# R202X.net
KiCad netlist of a schematic drawn in EAGLE
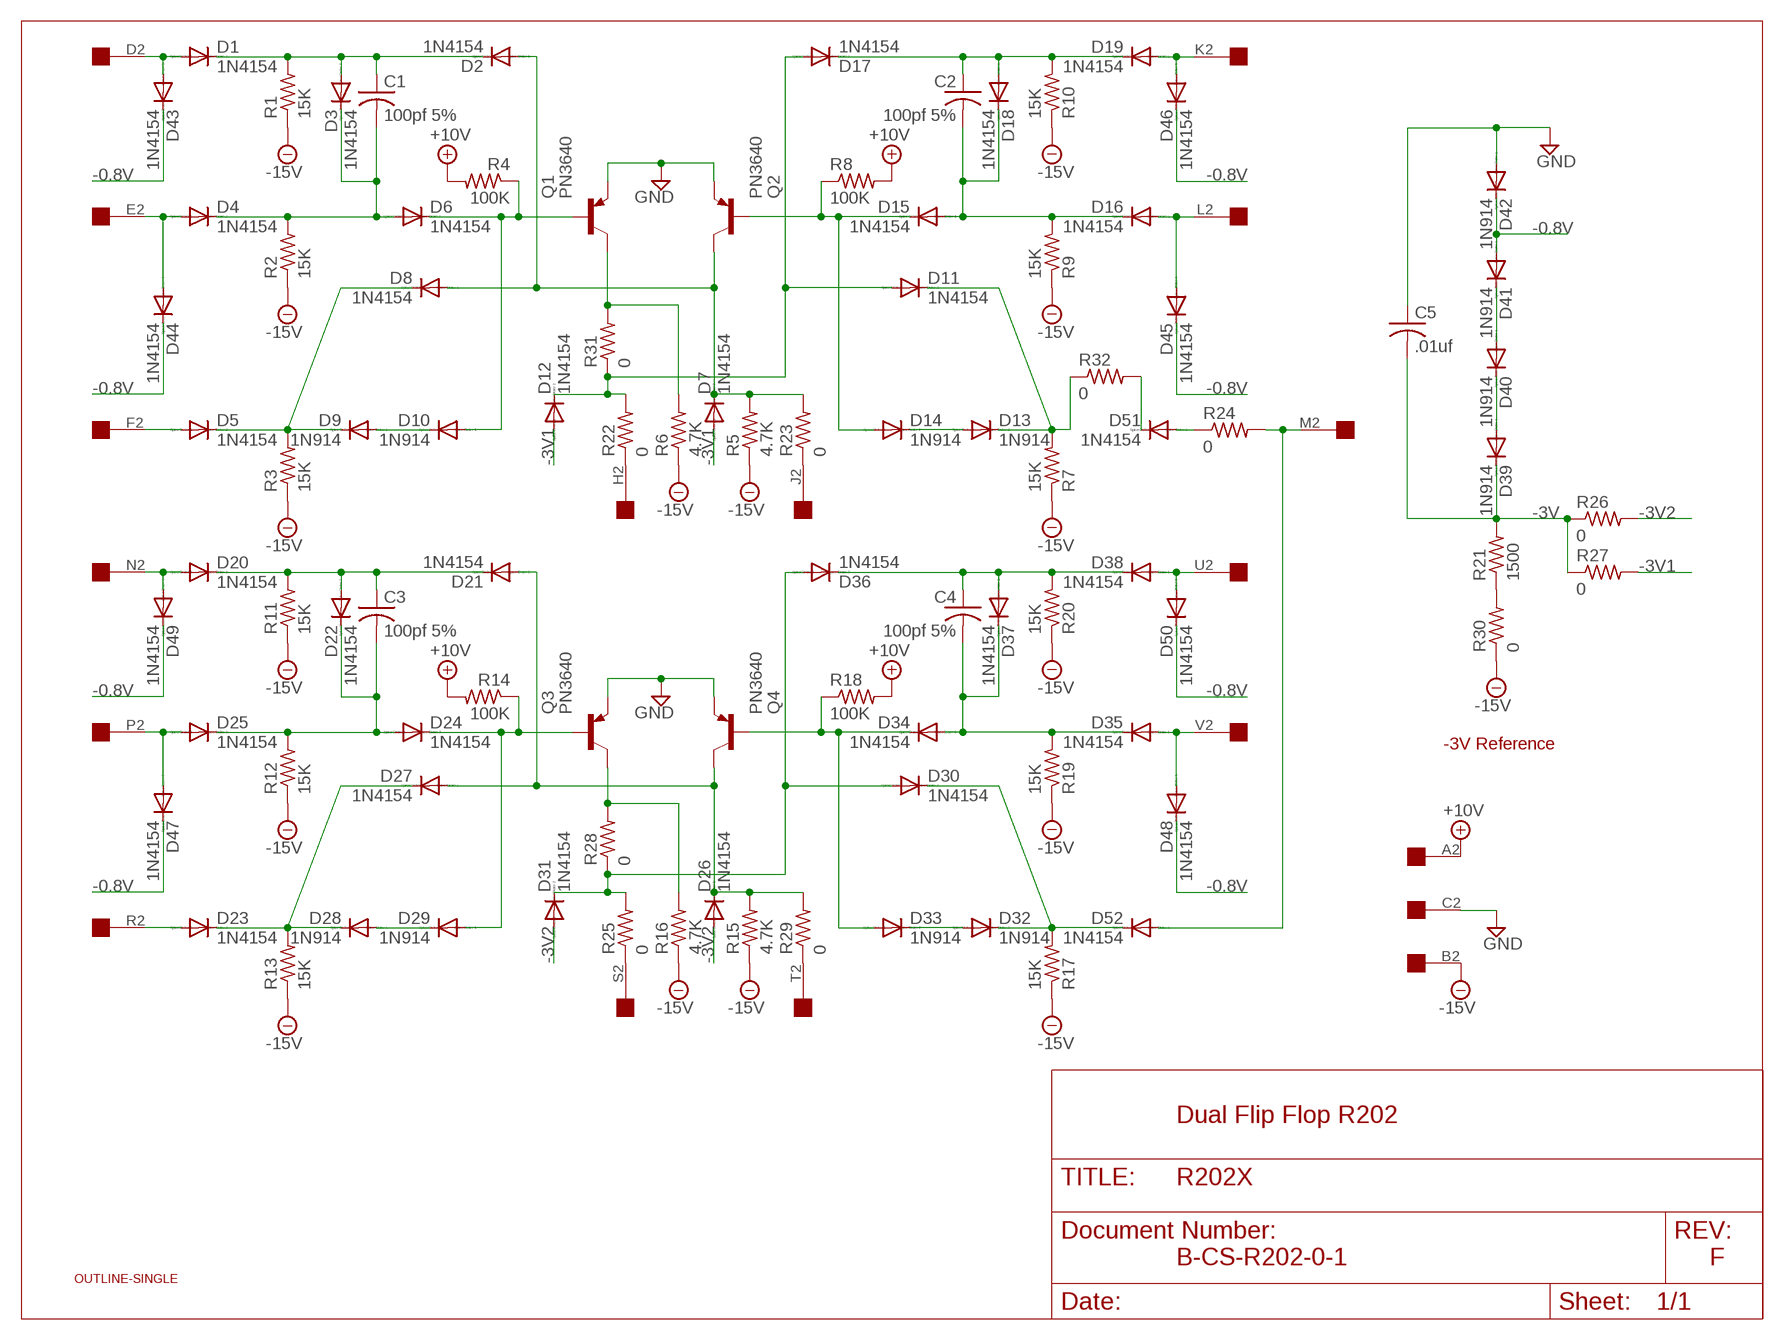
[diagram p0: schematic, sheet 1]

(export (version "E")
  (design (tool "Eeschema 10.0.6"))
  (components
    (comp (ref "C1")
      (value "100pf 5%")
      (footprint "eagle-import:C050-025X075")
      (libsource (lib "eagle-import") (part "C-US050-025X075"))
    )
    (comp (ref "C2")
      (value "100pf 5%")
      (footprint "eagle-import:C050-025X075")
      (libsource (lib "eagle-import") (part "C-US050-025X075"))
    )
    (comp (ref "C3")
      (value "100pf 5%")
      (footprint "eagle-import:C050-025X075")
      (libsource (lib "eagle-import") (part "C-US050-025X075"))
    )
    (comp (ref "C4")
      (value "100pf 5%")
      (footprint "eagle-import:C050-025X075")
      (libsource (lib "eagle-import") (part "C-US050-025X075"))
    )
    (comp (ref "C5")
      (value ".01uf")
      (footprint "eagle-import:C050-025X075")
      (libsource (lib "eagle-import") (part "C-US050-025X075"))
    )
    (comp (ref "D1")
      (value "1N4154")
      (footprint "eagle-import:DO35-10")
      (libsource (lib "eagle-import") (part "1N4148DO35-10"))
    )
    (comp (ref "D2")
      (value "1N4154")
      (footprint "eagle-import:DO35-10")
      (libsource (lib "eagle-import") (part "1N4148DO35-10"))
    )
    (comp (ref "D3")
      (value "1N4154")
      (footprint "eagle-import:DO35-10")
      (libsource (lib "eagle-import") (part "1N4148DO35-10"))
    )
    (comp (ref "D4")
      (value "1N4154")
      (footprint "eagle-import:DO35-10")
      (libsource (lib "eagle-import") (part "1N4148DO35-10"))
    )
    (comp (ref "D5")
      (value "1N4154")
      (footprint "eagle-import:DO35-10")
      (libsource (lib "eagle-import") (part "1N4148DO35-10"))
    )
    (comp (ref "D6")
      (value "1N4154")
      (footprint "eagle-import:DO35-10")
      (libsource (lib "eagle-import") (part "1N4148DO35-10"))
    )
    (comp (ref "D7")
      (value "1N4154")
      (footprint "eagle-import:DO35-10")
      (libsource (lib "eagle-import") (part "1N4148DO35-10"))
    )
    (comp (ref "D8")
      (value "1N4154")
      (footprint "eagle-import:DO35-10")
      (libsource (lib "eagle-import") (part "1N4148DO35-10"))
    )
    (comp (ref "D9")
      (value "1N914")
      (footprint "eagle-import:DO35-10")
      (libsource (lib "eagle-import") (part "1N4148DO35-10"))
    )
    (comp (ref "D10")
      (value "1N914")
      (footprint "eagle-import:DO35-10")
      (libsource (lib "eagle-import") (part "1N4148DO35-10"))
    )
    (comp (ref "D11")
      (value "1N4154")
      (footprint "eagle-import:DO35-10")
      (libsource (lib "eagle-import") (part "1N4148DO35-10"))
    )
    (comp (ref "D12")
      (value "1N4154")
      (footprint "eagle-import:DO35-10")
      (libsource (lib "eagle-import") (part "1N4148DO35-10"))
    )
    (comp (ref "D13")
      (value "1N914")
      (footprint "eagle-import:DO35-10")
      (libsource (lib "eagle-import") (part "1N4148DO35-10"))
    )
    (comp (ref "D14")
      (value "1N914")
      (footprint "eagle-import:DO35-10")
      (libsource (lib "eagle-import") (part "1N4148DO35-10"))
    )
    (comp (ref "D15")
      (value "1N4154")
      (footprint "eagle-import:DO35-10")
      (libsource (lib "eagle-import") (part "1N4148DO35-10"))
    )
    (comp (ref "D16")
      (value "1N4154")
      (footprint "eagle-import:DO35-10")
      (libsource (lib "eagle-import") (part "1N4148DO35-10"))
    )
    (comp (ref "D17")
      (value "1N4154")
      (footprint "eagle-import:DO35-10")
      (libsource (lib "eagle-import") (part "1N4148DO35-10"))
    )
    (comp (ref "D18")
      (value "1N4154")
      (footprint "eagle-import:DO35-10")
      (libsource (lib "eagle-import") (part "1N4148DO35-10"))
    )
    (comp (ref "D19")
      (value "1N4154")
      (footprint "eagle-import:DO35-10")
      (libsource (lib "eagle-import") (part "1N4148DO35-10"))
    )
    (comp (ref "D20")
      (value "1N4154")
      (footprint "eagle-import:DO35-10")
      (libsource (lib "eagle-import") (part "1N4148DO35-10"))
    )
    (comp (ref "D21")
      (value "1N4154")
      (footprint "eagle-import:DO35-10")
      (libsource (lib "eagle-import") (part "1N4148DO35-10"))
    )
    (comp (ref "D22")
      (value "1N4154")
      (footprint "eagle-import:DO35-10")
      (libsource (lib "eagle-import") (part "1N4148DO35-10"))
    )
    (comp (ref "D23")
      (value "1N4154")
      (footprint "eagle-import:DO35-10")
      (libsource (lib "eagle-import") (part "1N4148DO35-10"))
    )
    (comp (ref "D24")
      (value "1N4154")
      (footprint "eagle-import:DO35-10")
      (libsource (lib "eagle-import") (part "1N4148DO35-10"))
    )
    (comp (ref "D25")
      (value "1N4154")
      (footprint "eagle-import:DO35-10")
      (libsource (lib "eagle-import") (part "1N4148DO35-10"))
    )
    (comp (ref "D26")
      (value "1N4154")
      (footprint "eagle-import:DO35-10")
      (libsource (lib "eagle-import") (part "1N4148DO35-10"))
    )
    (comp (ref "D27")
      (value "1N4154")
      (footprint "eagle-import:DO35-10")
      (libsource (lib "eagle-import") (part "1N4148DO35-10"))
    )
    (comp (ref "D28")
      (value "1N914")
      (footprint "eagle-import:DO35-10")
      (libsource (lib "eagle-import") (part "1N4148DO35-10"))
    )
    (comp (ref "D29")
      (value "1N914")
      (footprint "eagle-import:DO35-10")
      (libsource (lib "eagle-import") (part "1N4148DO35-10"))
    )
    (comp (ref "D30")
      (value "1N4154")
      (footprint "eagle-import:DO35-10")
      (libsource (lib "eagle-import") (part "1N4148DO35-10"))
    )
    (comp (ref "D31")
      (value "1N4154")
      (footprint "eagle-import:DO35-10")
      (libsource (lib "eagle-import") (part "1N4148DO35-10"))
    )
    (comp (ref "D32")
      (value "1N914")
      (footprint "eagle-import:DO35-10")
      (libsource (lib "eagle-import") (part "1N4148DO35-10"))
    )
    (comp (ref "D33")
      (value "1N914")
      (footprint "eagle-import:DO35-10")
      (libsource (lib "eagle-import") (part "1N4148DO35-10"))
    )
    (comp (ref "D34")
      (value "1N4154")
      (footprint "eagle-import:DO35-10")
      (libsource (lib "eagle-import") (part "1N4148DO35-10"))
    )
    (comp (ref "D35")
      (value "1N4154")
      (footprint "eagle-import:DO35-10")
      (libsource (lib "eagle-import") (part "1N4148DO35-10"))
    )
    (comp (ref "D36")
      (value "1N4154")
      (footprint "eagle-import:DO35-10")
      (libsource (lib "eagle-import") (part "1N4148DO35-10"))
    )
    (comp (ref "D37")
      (value "1N4154")
      (footprint "eagle-import:DO35-10")
      (libsource (lib "eagle-import") (part "1N4148DO35-10"))
    )
    (comp (ref "D38")
      (value "1N4154")
      (footprint "eagle-import:DO35-10")
      (libsource (lib "eagle-import") (part "1N4148DO35-10"))
    )
    (comp (ref "D39")
      (value "1N914")
      (footprint "eagle-import:DO35-10")
      (libsource (lib "eagle-import") (part "1N4148DO35-10"))
    )
    (comp (ref "D40")
      (value "1N914")
      (footprint "eagle-import:DO35-10")
      (libsource (lib "eagle-import") (part "1N4148DO35-10"))
    )
    (comp (ref "D41")
      (value "1N914")
      (footprint "eagle-import:DO35-10")
      (libsource (lib "eagle-import") (part "1N4148DO35-10"))
    )
    (comp (ref "D42")
      (value "1N914")
      (footprint "eagle-import:DO35-10")
      (libsource (lib "eagle-import") (part "1N4148DO35-10"))
    )
    (comp (ref "D43")
      (value "1N4154")
      (footprint "eagle-import:DO35-10")
      (libsource (lib "eagle-import") (part "1N4148DO35-10"))
    )
    (comp (ref "D44")
      (value "1N4154")
      (footprint "eagle-import:DO35-10")
      (libsource (lib "eagle-import") (part "1N4148DO35-10"))
    )
    (comp (ref "D45")
      (value "1N4154")
      (footprint "eagle-import:DO35-10")
      (libsource (lib "eagle-import") (part "1N4148DO35-10"))
    )
    (comp (ref "D46")
      (value "1N4154")
      (footprint "eagle-import:DO35-10")
      (libsource (lib "eagle-import") (part "1N4148DO35-10"))
    )
    (comp (ref "D47")
      (value "1N4154")
      (footprint "eagle-import:DO35-10")
      (libsource (lib "eagle-import") (part "1N4148DO35-10"))
    )
    (comp (ref "D48")
      (value "1N4154")
      (footprint "eagle-import:DO35-10")
      (libsource (lib "eagle-import") (part "1N4148DO35-10"))
    )
    (comp (ref "D49")
      (value "1N4154")
      (footprint "eagle-import:DO35-10")
      (libsource (lib "eagle-import") (part "1N4148DO35-10"))
    )
    (comp (ref "D50")
      (value "1N4154")
      (footprint "eagle-import:DO35-10")
      (libsource (lib "eagle-import") (part "1N4148DO35-10"))
    )
    (comp (ref "D51")
      (value "1N4154")
      (footprint "eagle-import:DO35-10")
      (libsource (lib "eagle-import") (part "1N4148DO35-10"))
    )
    (comp (ref "D52")
      (value "1N4154")
      (footprint "eagle-import:DO35-10")
      (libsource (lib "eagle-import") (part "1N4148DO35-10"))
    )
    (comp (ref "Q1")
      (value "PN3640")
      (footprint "eagle-import:TO39")
      (libsource (lib "eagle-import") (part "2N3637"))
    )
    (comp (ref "Q2")
      (value "PN3640")
      (footprint "eagle-import:TO39")
      (libsource (lib "eagle-import") (part "2N3637"))
    )
    (comp (ref "Q3")
      (value "PN3640")
      (footprint "eagle-import:TO39")
      (libsource (lib "eagle-import") (part "2N3637"))
    )
    (comp (ref "Q4")
      (value "PN3640")
      (footprint "eagle-import:TO39")
      (libsource (lib "eagle-import") (part "2N3637"))
    )
    (comp (ref "R1")
      (value "15K")
      (footprint "eagle-import:0207_10")
      (libsource (lib "eagle-import") (part "R-US_0207/10"))
    )
    (comp (ref "R2")
      (value "15K")
      (footprint "eagle-import:0207_10")
      (libsource (lib "eagle-import") (part "R-US_0207/10"))
    )
    (comp (ref "R3")
      (value "15K")
      (footprint "eagle-import:0207_10")
      (libsource (lib "eagle-import") (part "R-US_0207/10"))
    )
    (comp (ref "R4")
      (value "100K")
      (footprint "eagle-import:0207_10")
      (libsource (lib "eagle-import") (part "R-US_0207/10"))
    )
    (comp (ref "R5")
      (value "4.7K")
      (footprint "eagle-import:0207_10")
      (libsource (lib "eagle-import") (part "R-US_0207/10"))
    )
    (comp (ref "R6")
      (value "4.7K")
      (footprint "eagle-import:0207_10")
      (libsource (lib "eagle-import") (part "R-US_0207/10"))
    )
    (comp (ref "R7")
      (value "15K")
      (footprint "eagle-import:0207_10")
      (libsource (lib "eagle-import") (part "R-US_0207/10"))
    )
    (comp (ref "R8")
      (value "100K")
      (footprint "eagle-import:0207_10")
      (libsource (lib "eagle-import") (part "R-US_0207/10"))
    )
    (comp (ref "R9")
      (value "15K")
      (footprint "eagle-import:0207_10")
      (libsource (lib "eagle-import") (part "R-US_0207/10"))
    )
    (comp (ref "R10")
      (value "15K")
      (footprint "eagle-import:0207_10")
      (libsource (lib "eagle-import") (part "R-US_0207/10"))
    )
    (comp (ref "R11")
      (value "15K")
      (footprint "eagle-import:0207_10")
      (libsource (lib "eagle-import") (part "R-US_0207/10"))
    )
    (comp (ref "R12")
      (value "15K")
      (footprint "eagle-import:0207_10")
      (libsource (lib "eagle-import") (part "R-US_0207/10"))
    )
    (comp (ref "R13")
      (value "15K")
      (footprint "eagle-import:0207_10")
      (libsource (lib "eagle-import") (part "R-US_0207/10"))
    )
    (comp (ref "R14")
      (value "100K")
      (footprint "eagle-import:0207_10")
      (libsource (lib "eagle-import") (part "R-US_0207/10"))
    )
    (comp (ref "R15")
      (value "4.7K")
      (footprint "eagle-import:0207_10")
      (libsource (lib "eagle-import") (part "R-US_0207/10"))
    )
    (comp (ref "R16")
      (value "4.7K")
      (footprint "eagle-import:0207_10")
      (libsource (lib "eagle-import") (part "R-US_0207/10"))
    )
    (comp (ref "R17")
      (value "15K")
      (footprint "eagle-import:0207_10")
      (libsource (lib "eagle-import") (part "R-US_0207/10"))
    )
    (comp (ref "R18")
      (value "100K")
      (footprint "eagle-import:0207_10")
      (libsource (lib "eagle-import") (part "R-US_0207/10"))
    )
    (comp (ref "R19")
      (value "15K")
      (footprint "eagle-import:0207_10")
      (libsource (lib "eagle-import") (part "R-US_0207/10"))
    )
    (comp (ref "R20")
      (value "15K")
      (footprint "eagle-import:0207_10")
      (libsource (lib "eagle-import") (part "R-US_0207/10"))
    )
    (comp (ref "R21")
      (value "1500")
      (footprint "eagle-import:0207_10")
      (libsource (lib "eagle-import") (part "R-US_0207/10"))
    )
    (comp (ref "R22")
      (value "0")
      (footprint "eagle-import:0207_10")
      (libsource (lib "eagle-import") (part "R-US_0207/10"))
    )
    (comp (ref "R23")
      (value "0")
      (footprint "eagle-import:0207_10")
      (libsource (lib "eagle-import") (part "R-US_0207/10"))
    )
    (comp (ref "R24")
      (value "0")
      (footprint "eagle-import:0207_10")
      (libsource (lib "eagle-import") (part "R-US_0207/10"))
    )
    (comp (ref "R25")
      (value "0")
      (footprint "eagle-import:0207_10")
      (libsource (lib "eagle-import") (part "R-US_0207/10"))
    )
    (comp (ref "R26")
      (value "0")
      (footprint "eagle-import:0207_10")
      (libsource (lib "eagle-import") (part "R-US_0207/10"))
    )
    (comp (ref "R27")
      (value "0")
      (footprint "eagle-import:0207_10")
      (libsource (lib "eagle-import") (part "R-US_0207/10"))
    )
    (comp (ref "R28")
      (value "0")
      (footprint "eagle-import:0207_10")
      (libsource (lib "eagle-import") (part "R-US_0207/10"))
    )
    (comp (ref "R29")
      (value "0")
      (footprint "eagle-import:0207_10")
      (libsource (lib "eagle-import") (part "R-US_0207/10"))
    )
    (comp (ref "R30")
      (value "0")
      (footprint "eagle-import:0207_10")
      (libsource (lib "eagle-import") (part "R-US_0207/10"))
    )
    (comp (ref "R31")
      (value "0")
      (footprint "eagle-import:0207_10")
      (libsource (lib "eagle-import") (part "R-US_0207/10"))
    )
    (comp (ref "R32")
      (value "0")
      (footprint "eagle-import:0207_10")
      (libsource (lib "eagle-import") (part "R-US_0207/10"))
    )
    (comp (ref "U$1")
      (value "OUTLINE-SINGLE")
      (footprint "eagle-import:SINGLE")
      (libsource (lib "eagle-import") (part "OUTLINE-SINGLE"))
    )
    (comp (ref "U$2")
      (value "EDGE-1")
      (footprint "eagle-import:EDGE-CON1")
      (libsource (lib "eagle-import") (part "EDGE-1"))
    )
  )
  (nets
    (net (code "1") (name "+10V") (class "Default")
      (node (ref "R14") (pin "2") (pinfunction "2_2") (pintype "passive"))
      (node (ref "R18") (pin "2") (pinfunction "2_2") (pintype "passive"))
      (node (ref "R4") (pin "2") (pinfunction "2_2") (pintype "passive"))
      (node (ref "R8") (pin "2") (pinfunction "2_2") (pintype "passive"))
      (node (ref "U$2") (pin "A2") (pinfunction "1_A2") (pintype "bidirectional"))
    )
    (net (code "2") (name "-15V") (class "Default")
      (node (ref "R1") (pin "1") (pinfunction "1_1") (pintype "passive"))
      (node (ref "R10") (pin "1") (pinfunction "1_1") (pintype "passive"))
      (node (ref "R11") (pin "1") (pinfunction "1_1") (pintype "passive"))
      (node (ref "R12") (pin "1") (pinfunction "1_1") (pintype "passive"))
      (node (ref "R13") (pin "1") (pinfunction "1_1") (pintype "passive"))
      (node (ref "R15") (pin "1") (pinfunction "1_1") (pintype "passive"))
      (node (ref "R16") (pin "1") (pinfunction "1_1") (pintype "passive"))
      (node (ref "R17") (pin "1") (pinfunction "1_1") (pintype "passive"))
      (node (ref "R19") (pin "1") (pinfunction "1_1") (pintype "passive"))
      (node (ref "R2") (pin "1") (pinfunction "1_1") (pintype "passive"))
      (node (ref "R20") (pin "1") (pinfunction "1_1") (pintype "passive"))
      (node (ref "R3") (pin "1") (pinfunction "1_1") (pintype "passive"))
      (node (ref "R30") (pin "1") (pinfunction "1_1") (pintype "passive"))
      (node (ref "R5") (pin "1") (pinfunction "1_1") (pintype "passive"))
      (node (ref "R6") (pin "1") (pinfunction "1_1") (pintype "passive"))
      (node (ref "R7") (pin "1") (pinfunction "1_1") (pintype "passive"))
      (node (ref "R9") (pin "1") (pinfunction "1_1") (pintype "passive"))
      (node (ref "U$2") (pin "B2") (pinfunction "1_B2") (pintype "bidirectional"))
    )
    (net (code "3") (name "/-0.8V") (class "Default")
      (node (ref "D41") (pin "A") (pinfunction "A_A") (pintype "passive"))
      (node (ref "D42") (pin "C") (pinfunction "C_C") (pintype "passive"))
      (node (ref "D43") (pin "C") (pinfunction "C_C") (pintype "passive"))
      (node (ref "D44") (pin "C") (pinfunction "C_C") (pintype "passive"))
      (node (ref "D45") (pin "C") (pinfunction "C_C") (pintype "passive"))
      (node (ref "D46") (pin "C") (pinfunction "C_C") (pintype "passive"))
      (node (ref "D47") (pin "C") (pinfunction "C_C") (pintype "passive"))
      (node (ref "D48") (pin "C") (pinfunction "C_C") (pintype "passive"))
      (node (ref "D49") (pin "C") (pinfunction "C_C") (pintype "passive"))
      (node (ref "D50") (pin "C") (pinfunction "C_C") (pintype "passive"))
    )
    (net (code "4") (name "/-3V") (class "Default")
      (node (ref "C5") (pin "2") (pinfunction "2_2") (pintype "passive"))
      (node (ref "D39") (pin "C") (pinfunction "C_C") (pintype "passive"))
      (node (ref "R21") (pin "2") (pinfunction "2_2") (pintype "passive"))
      (node (ref "R26") (pin "1") (pinfunction "1_1") (pintype "passive"))
      (node (ref "R27") (pin "1") (pinfunction "1_1") (pintype "passive"))
    )
    (net (code "5") (name "/-3V1") (class "Default")
      (node (ref "D12") (pin "A") (pinfunction "A_A") (pintype "passive"))
      (node (ref "D7") (pin "A") (pinfunction "A_A") (pintype "passive"))
      (node (ref "R27") (pin "2") (pinfunction "2_2") (pintype "passive"))
    )
    (net (code "6") (name "/-3V2") (class "Default")
      (node (ref "D26") (pin "A") (pinfunction "A_A") (pintype "passive"))
      (node (ref "D31") (pin "A") (pinfunction "A_A") (pintype "passive"))
      (node (ref "R26") (pin "2") (pinfunction "2_2") (pintype "passive"))
    )
    (net (code "7") (name "GND") (class "Default")
      (node (ref "C5") (pin "1") (pinfunction "1_1") (pintype "passive"))
      (node (ref "D42") (pin "A") (pinfunction "A_A") (pintype "passive"))
      (node (ref "Q1") (pin "1") (pinfunction "E_1") (pintype "passive"))
      (node (ref "Q2") (pin "1") (pinfunction "E_1") (pintype "passive"))
      (node (ref "Q3") (pin "1") (pinfunction "E_1") (pintype "passive"))
      (node (ref "Q4") (pin "1") (pinfunction "E_1") (pintype "passive"))
      (node (ref "U$2") (pin "C2") (pinfunction "1_C2") (pintype "bidirectional"))
    )
    (net (code "8") (name "Net-(C1-Pad1)") (class "Default")
      (node (ref "C1") (pin "1") (pinfunction "1_1") (pintype "passive"))
      (node (ref "D1") (pin "C") (pinfunction "C_C") (pintype "passive"))
      (node (ref "D2") (pin "C") (pinfunction "C_C") (pintype "passive"))
      (node (ref "D3") (pin "A") (pinfunction "A_A") (pintype "passive"))
      (node (ref "R1") (pin "2") (pinfunction "2_2") (pintype "passive"))
    )
    (net (code "9") (name "Net-(C1-Pad2)") (class "Default")
      (node (ref "C1") (pin "2") (pinfunction "2_2") (pintype "passive"))
      (node (ref "D3") (pin "C") (pinfunction "C_C") (pintype "passive"))
      (node (ref "D4") (pin "C") (pinfunction "C_C") (pintype "passive"))
      (node (ref "D6") (pin "A") (pinfunction "A_A") (pintype "passive"))
      (node (ref "R2") (pin "2") (pinfunction "2_2") (pintype "passive"))
    )
    (net (code "10") (name "Net-(C2-Pad1)") (class "Default")
      (node (ref "C2") (pin "1") (pinfunction "1_1") (pintype "passive"))
      (node (ref "D17") (pin "C") (pinfunction "C_C") (pintype "passive"))
      (node (ref "D18") (pin "A") (pinfunction "A_A") (pintype "passive"))
      (node (ref "D19") (pin "C") (pinfunction "C_C") (pintype "passive"))
      (node (ref "R10") (pin "2") (pinfunction "2_2") (pintype "passive"))
    )
    (net (code "11") (name "Net-(C2-Pad2)") (class "Default")
      (node (ref "C2") (pin "2") (pinfunction "2_2") (pintype "passive"))
      (node (ref "D15") (pin "A") (pinfunction "A_A") (pintype "passive"))
      (node (ref "D16") (pin "C") (pinfunction "C_C") (pintype "passive"))
      (node (ref "D18") (pin "C") (pinfunction "C_C") (pintype "passive"))
      (node (ref "R9") (pin "2") (pinfunction "2_2") (pintype "passive"))
    )
    (net (code "12") (name "Net-(C3-Pad1)") (class "Default")
      (node (ref "C3") (pin "1") (pinfunction "1_1") (pintype "passive"))
      (node (ref "D20") (pin "C") (pinfunction "C_C") (pintype "passive"))
      (node (ref "D21") (pin "C") (pinfunction "C_C") (pintype "passive"))
      (node (ref "D22") (pin "A") (pinfunction "A_A") (pintype "passive"))
      (node (ref "R11") (pin "2") (pinfunction "2_2") (pintype "passive"))
    )
    (net (code "13") (name "Net-(C3-Pad2)") (class "Default")
      (node (ref "C3") (pin "2") (pinfunction "2_2") (pintype "passive"))
      (node (ref "D22") (pin "C") (pinfunction "C_C") (pintype "passive"))
      (node (ref "D24") (pin "A") (pinfunction "A_A") (pintype "passive"))
      (node (ref "D25") (pin "C") (pinfunction "C_C") (pintype "passive"))
      (node (ref "R12") (pin "2") (pinfunction "2_2") (pintype "passive"))
    )
    (net (code "14") (name "Net-(C4-Pad1)") (class "Default")
      (node (ref "C4") (pin "1") (pinfunction "1_1") (pintype "passive"))
      (node (ref "D36") (pin "C") (pinfunction "C_C") (pintype "passive"))
      (node (ref "D37") (pin "A") (pinfunction "A_A") (pintype "passive"))
      (node (ref "D38") (pin "C") (pinfunction "C_C") (pintype "passive"))
      (node (ref "R20") (pin "2") (pinfunction "2_2") (pintype "passive"))
    )
    (net (code "15") (name "Net-(C4-Pad2)") (class "Default")
      (node (ref "C4") (pin "2") (pinfunction "2_2") (pintype "passive"))
      (node (ref "D34") (pin "A") (pinfunction "A_A") (pintype "passive"))
      (node (ref "D35") (pin "C") (pinfunction "C_C") (pintype "passive"))
      (node (ref "D37") (pin "C") (pinfunction "C_C") (pintype "passive"))
      (node (ref "R19") (pin "2") (pinfunction "2_2") (pintype "passive"))
    )
    (net (code "16") (name "Net-(D5-PadC)") (class "Default")
      (node (ref "D5") (pin "C") (pinfunction "C_C") (pintype "passive"))
      (node (ref "D8") (pin "C") (pinfunction "C_C") (pintype "passive"))
      (node (ref "D9") (pin "C") (pinfunction "C_C") (pintype "passive"))
      (node (ref "R3") (pin "2") (pinfunction "2_2") (pintype "passive"))
    )
    (net (code "17") (name "Net-(D10-PadC)") (class "Default")
      (node (ref "D10") (pin "C") (pinfunction "C_C") (pintype "passive"))
      (node (ref "D9") (pin "A") (pinfunction "A_A") (pintype "passive"))
    )
    (net (code "18") (name "Net-(D11-PadA)") (class "Default")
      (node (ref "D11") (pin "A") (pinfunction "A_A") (pintype "passive"))
      (node (ref "D12") (pin "C") (pinfunction "C_C") (pintype "passive"))
      (node (ref "D17") (pin "A") (pinfunction "A_A") (pintype "passive"))
      (node (ref "R22") (pin "2") (pinfunction "2_2") (pintype "passive"))
      (node (ref "R31") (pin "1") (pinfunction "1_1") (pintype "passive"))
    )
    (net (code "19") (name "Net-(D11-PadC)") (class "Default")
      (node (ref "D11") (pin "C") (pinfunction "C_C") (pintype "passive"))
      (node (ref "D13") (pin "C") (pinfunction "C_C") (pintype "passive"))
      (node (ref "R32") (pin "1") (pinfunction "1_1") (pintype "passive"))
      (node (ref "R7") (pin "2") (pinfunction "2_2") (pintype "passive"))
    )
    (net (code "20") (name "Net-(D13-PadA)") (class "Default")
      (node (ref "D13") (pin "A") (pinfunction "A_A") (pintype "passive"))
      (node (ref "D14") (pin "C") (pinfunction "C_C") (pintype "passive"))
    )
    (net (code "21") (name "Net-(D23-PadC)") (class "Default")
      (node (ref "D23") (pin "C") (pinfunction "C_C") (pintype "passive"))
      (node (ref "D27") (pin "C") (pinfunction "C_C") (pintype "passive"))
      (node (ref "D28") (pin "C") (pinfunction "C_C") (pintype "passive"))
      (node (ref "R13") (pin "2") (pinfunction "2_2") (pintype "passive"))
    )
    (net (code "22") (name "Net-(D28-PadA)") (class "Default")
      (node (ref "D28") (pin "A") (pinfunction "A_A") (pintype "passive"))
      (node (ref "D29") (pin "C") (pinfunction "C_C") (pintype "passive"))
    )
    (net (code "23") (name "Net-(D30-PadA)") (class "Default")
      (node (ref "D30") (pin "A") (pinfunction "A_A") (pintype "passive"))
      (node (ref "D31") (pin "C") (pinfunction "C_C") (pintype "passive"))
      (node (ref "D36") (pin "A") (pinfunction "A_A") (pintype "passive"))
      (node (ref "R25") (pin "2") (pinfunction "2_2") (pintype "passive"))
      (node (ref "R28") (pin "1") (pinfunction "1_1") (pintype "passive"))
    )
    (net (code "24") (name "Net-(D30-PadC)") (class "Default")
      (node (ref "D30") (pin "C") (pinfunction "C_C") (pintype "passive"))
      (node (ref "D32") (pin "C") (pinfunction "C_C") (pintype "passive"))
      (node (ref "D52") (pin "C") (pinfunction "C_C") (pintype "passive"))
      (node (ref "R17") (pin "2") (pinfunction "2_2") (pintype "passive"))
    )
    (net (code "25") (name "Net-(D32-PadA)") (class "Default")
      (node (ref "D32") (pin "A") (pinfunction "A_A") (pintype "passive"))
      (node (ref "D33") (pin "C") (pinfunction "C_C") (pintype "passive"))
    )
    (net (code "26") (name "Net-(D39-PadA)") (class "Default")
      (node (ref "D39") (pin "A") (pinfunction "A_A") (pintype "passive"))
      (node (ref "D40") (pin "C") (pinfunction "C_C") (pintype "passive"))
    )
    (net (code "27") (name "Net-(D40-PadA)") (class "Default")
      (node (ref "D40") (pin "A") (pinfunction "A_A") (pintype "passive"))
      (node (ref "D41") (pin "C") (pinfunction "C_C") (pintype "passive"))
    )
    (net (code "28") (name "Net-(D51-PadA)") (class "Default")
      (node (ref "D51") (pin "A") (pinfunction "A_A") (pintype "passive"))
      (node (ref "R24") (pin "1") (pinfunction "1_1") (pintype "passive"))
    )
    (net (code "29") (name "Net-(D51-PadC)") (class "Default")
      (node (ref "D51") (pin "C") (pinfunction "C_C") (pintype "passive"))
      (node (ref "R32") (pin "2") (pinfunction "2_2") (pintype "passive"))
    )
    (net (code "30") (name "Net-(Q1-B)") (class "Default")
      (node (ref "D10") (pin "A") (pinfunction "A_A") (pintype "passive"))
      (node (ref "D6") (pin "C") (pinfunction "C_C") (pintype "passive"))
      (node (ref "Q1") (pin "2") (pinfunction "B_2") (pintype "passive"))
      (node (ref "R4") (pin "1") (pinfunction "1_1") (pintype "passive"))
    )
    (net (code "31") (name "Net-(Q1-C)") (class "Default")
      (node (ref "Q1") (pin "3") (pinfunction "C_3") (pintype "passive"))
      (node (ref "R31") (pin "2") (pinfunction "2_2") (pintype "passive"))
      (node (ref "R6") (pin "2") (pinfunction "2_2") (pintype "passive"))
    )
    (net (code "32") (name "Net-(Q2-B)") (class "Default")
      (node (ref "D14") (pin "A") (pinfunction "A_A") (pintype "passive"))
      (node (ref "D15") (pin "C") (pinfunction "C_C") (pintype "passive"))
      (node (ref "Q2") (pin "2") (pinfunction "B_2") (pintype "passive"))
      (node (ref "R8") (pin "1") (pinfunction "1_1") (pintype "passive"))
    )
    (net (code "33") (name "Net-(Q2-C)") (class "Default")
      (node (ref "D2") (pin "A") (pinfunction "A_A") (pintype "passive"))
      (node (ref "D7") (pin "C") (pinfunction "C_C") (pintype "passive"))
      (node (ref "D8") (pin "A") (pinfunction "A_A") (pintype "passive"))
      (node (ref "Q2") (pin "3") (pinfunction "C_3") (pintype "passive"))
      (node (ref "R23") (pin "2") (pinfunction "2_2") (pintype "passive"))
      (node (ref "R5") (pin "2") (pinfunction "2_2") (pintype "passive"))
    )
    (net (code "34") (name "Net-(Q3-B)") (class "Default")
      (node (ref "D24") (pin "C") (pinfunction "C_C") (pintype "passive"))
      (node (ref "D29") (pin "A") (pinfunction "A_A") (pintype "passive"))
      (node (ref "Q3") (pin "2") (pinfunction "B_2") (pintype "passive"))
      (node (ref "R14") (pin "1") (pinfunction "1_1") (pintype "passive"))
    )
    (net (code "35") (name "Net-(Q3-C)") (class "Default")
      (node (ref "Q3") (pin "3") (pinfunction "C_3") (pintype "passive"))
      (node (ref "R16") (pin "2") (pinfunction "2_2") (pintype "passive"))
      (node (ref "R28") (pin "2") (pinfunction "2_2") (pintype "passive"))
    )
    (net (code "36") (name "Net-(Q4-B)") (class "Default")
      (node (ref "D33") (pin "A") (pinfunction "A_A") (pintype "passive"))
      (node (ref "D34") (pin "C") (pinfunction "C_C") (pintype "passive"))
      (node (ref "Q4") (pin "2") (pinfunction "B_2") (pintype "passive"))
      (node (ref "R18") (pin "1") (pinfunction "1_1") (pintype "passive"))
    )
    (net (code "37") (name "Net-(Q4-C)") (class "Default")
      (node (ref "D21") (pin "A") (pinfunction "A_A") (pintype "passive"))
      (node (ref "D26") (pin "C") (pinfunction "C_C") (pintype "passive"))
      (node (ref "D27") (pin "A") (pinfunction "A_A") (pintype "passive"))
      (node (ref "Q4") (pin "3") (pinfunction "C_3") (pintype "passive"))
      (node (ref "R15") (pin "2") (pinfunction "2_2") (pintype "passive"))
      (node (ref "R29") (pin "2") (pinfunction "2_2") (pintype "passive"))
    )
    (net (code "38") (name "Net-(R21-Pad1)") (class "Default")
      (node (ref "R21") (pin "1") (pinfunction "1_1") (pintype "passive"))
      (node (ref "R30") (pin "2") (pinfunction "2_2") (pintype "passive"))
    )
    (net (code "39") (name "Net-(U$2D-1)") (class "Default")
      (node (ref "D1") (pin "A") (pinfunction "A_A") (pintype "passive"))
      (node (ref "D43") (pin "A") (pinfunction "A_A") (pintype "passive"))
      (node (ref "U$2") (pin "D2") (pinfunction "1_D2") (pintype "bidirectional"))
    )
    (net (code "40") (name "Net-(U$2E-1)") (class "Default")
      (node (ref "D4") (pin "A") (pinfunction "A_A") (pintype "passive"))
      (node (ref "D44") (pin "A") (pinfunction "A_A") (pintype "passive"))
      (node (ref "U$2") (pin "E2") (pinfunction "1_E2") (pintype "bidirectional"))
    )
    (net (code "41") (name "Net-(U$2F-1)") (class "Default")
      (node (ref "D5") (pin "A") (pinfunction "A_A") (pintype "passive"))
      (node (ref "U$2") (pin "F2") (pinfunction "1_F2") (pintype "bidirectional"))
    )
    (net (code "42") (name "Net-(U$2G-1)") (class "Default")
      (node (ref "R22") (pin "1") (pinfunction "1_1") (pintype "passive"))
      (node (ref "U$2") (pin "H2") (pinfunction "1_H2") (pintype "bidirectional"))
    )
    (net (code "43") (name "Net-(U$2H-1)") (class "Default")
      (node (ref "R23") (pin "1") (pinfunction "1_1") (pintype "passive"))
      (node (ref "U$2") (pin "J2") (pinfunction "1_J2") (pintype "bidirectional"))
    )
    (net (code "44") (name "Net-(U$2I-1)") (class "Default")
      (node (ref "D19") (pin "A") (pinfunction "A_A") (pintype "passive"))
      (node (ref "D46") (pin "A") (pinfunction "A_A") (pintype "passive"))
      (node (ref "U$2") (pin "K2") (pinfunction "1_K2") (pintype "bidirectional"))
    )
    (net (code "45") (name "Net-(U$2J-1)") (class "Default")
      (node (ref "D16") (pin "A") (pinfunction "A_A") (pintype "passive"))
      (node (ref "D45") (pin "A") (pinfunction "A_A") (pintype "passive"))
      (node (ref "U$2") (pin "L2") (pinfunction "1_L2") (pintype "bidirectional"))
    )
    (net (code "46") (name "Net-(U$2K-1)") (class "Default")
      (node (ref "D52") (pin "A") (pinfunction "A_A") (pintype "passive"))
      (node (ref "R24") (pin "2") (pinfunction "2_2") (pintype "passive"))
      (node (ref "U$2") (pin "M2") (pinfunction "1_M2") (pintype "bidirectional"))
    )
    (net (code "47") (name "Net-(U$2L-1)") (class "Default")
      (node (ref "D20") (pin "A") (pinfunction "A_A") (pintype "passive"))
      (node (ref "D49") (pin "A") (pinfunction "A_A") (pintype "passive"))
      (node (ref "U$2") (pin "N2") (pinfunction "1_N2") (pintype "bidirectional"))
    )
    (net (code "48") (name "Net-(U$2M-1)") (class "Default")
      (node (ref "D25") (pin "A") (pinfunction "A_A") (pintype "passive"))
      (node (ref "D47") (pin "A") (pinfunction "A_A") (pintype "passive"))
      (node (ref "U$2") (pin "P2") (pinfunction "1_P2") (pintype "bidirectional"))
    )
    (net (code "49") (name "Net-(U$2N-1)") (class "Default")
      (node (ref "D23") (pin "A") (pinfunction "A_A") (pintype "passive"))
      (node (ref "U$2") (pin "R2") (pinfunction "1_R2") (pintype "bidirectional"))
    )
    (net (code "50") (name "Net-(U$2O-1)") (class "Default")
      (node (ref "R25") (pin "1") (pinfunction "1_1") (pintype "passive"))
      (node (ref "U$2") (pin "S2") (pinfunction "1_S2") (pintype "bidirectional"))
    )
    (net (code "51") (name "Net-(U$2P-1)") (class "Default")
      (node (ref "R29") (pin "1") (pinfunction "1_1") (pintype "passive"))
      (node (ref "U$2") (pin "T2") (pinfunction "1_T2") (pintype "bidirectional"))
    )
    (net (code "52") (name "Net-(U$2Q-1)") (class "Default")
      (node (ref "D38") (pin "A") (pinfunction "A_A") (pintype "passive"))
      (node (ref "D50") (pin "A") (pinfunction "A_A") (pintype "passive"))
      (node (ref "U$2") (pin "U2") (pinfunction "1_U2") (pintype "bidirectional"))
    )
    (net (code "53") (name "Net-(U$2R-1)") (class "Default")
      (node (ref "D35") (pin "A") (pinfunction "A_A") (pintype "passive"))
      (node (ref "D48") (pin "A") (pinfunction "A_A") (pintype "passive"))
      (node (ref "U$2") (pin "V2") (pinfunction "1_V2") (pintype "bidirectional"))
    )
  )
)
